# soldering_station_handle.net
KiCad netlist of a schematic drawn in Altium Designer
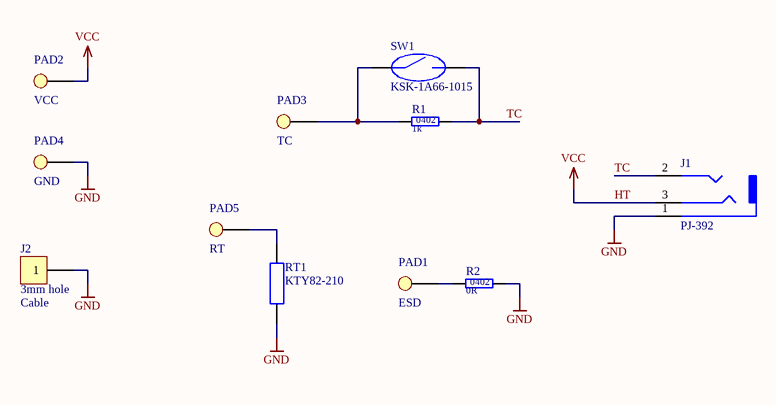
[diagram p0: soldering_station_handle.SchDoc]

(export (version "E")
  (design (tool "Eeschema 10.0.6"))
  (components
    (comp (ref "J1")
      (value "PJ-392")
      (footprint "PJ-392_Edge")
      (description "PCB Edge Mount")
      (libsource (lib "soldering_station") (part "PJ-392_Jack_Plug"))
    )
    (comp (ref "J2")
      (value "3mm hole")
      (footprint "J_HOLE3")
      (description "Single pin connector")
      (fields
        (field (name "PART NUMBER") "J_HOLE3")
        (field (name "SCH_FOOTPRINT") "Cable")
        (field (name "Comment") "Cable soldering")
      )
      (libsource (lib "Library") (part "J_PIN"))
    )
    (comp (ref "PAD1")
      (value "ESD")
      (footprint "PAD_08mm")
      (description "PCB Pad")
      (fields (field (name "PART NUMBER") "J_PAD"))
      (libsource (lib "Library") (part "PAD"))
    )
    (comp (ref "PAD2")
      (value "VCC")
      (footprint "PAD_08mm")
      (description "PCB Pad")
      (fields (field (name "PART NUMBER") "J_PAD"))
      (libsource (lib "Library") (part "PAD"))
    )
    (comp (ref "PAD3")
      (value "TC")
      (footprint "PAD_08mm")
      (description "PCB Pad")
      (fields (field (name "PART NUMBER") "J_PAD"))
      (libsource (lib "Library") (part "PAD"))
    )
    (comp (ref "PAD4")
      (value "GND")
      (footprint "PAD_08mm")
      (description "PCB Pad")
      (fields (field (name "PART NUMBER") "J_PAD"))
      (libsource (lib "Library") (part "PAD"))
    )
    (comp (ref "PAD5")
      (value "RT")
      (footprint "PAD_08mm")
      (description "PCB Pad")
      (fields (field (name "PART NUMBER") "J_PAD"))
      (libsource (lib "Library") (part "PAD"))
    )
    (comp (ref "R1")
      (value "1k")
      (footprint "R_0402_1005")
      (fields
        (field (name "SCH_FOOTPRINT") "0402")
        (field (name "PART NUMBER") "R_1k_0402_1")
        (field (name "VOLTAGE") "50V")
        (field (name "POWER") "63mW")
      )
      (libsource (lib "Library") (part "R"))
    )
    (comp (ref "R2")
      (value "0R")
      (footprint "R_0402_1005")
      (fields
        (field (name "SCH_FOOTPRINT") "0402")
        (field (name "PART NUMBER") "R_0R_0402_5")
        (field (name "VOLTAGE") "50V")
        (field (name "POWER") "100mW")
      )
      (libsource (lib "Library") (part "R"))
    )
    (comp (ref "RT1")
      (value "KTY82-210")
      (footprint "KTY82-210")
      (description "Czujnik temperatury; -55÷150°C; SOT23; SMD; 1,98kΩ")
      (libsource (lib "soldering_station") (part "KTY82-210"))
    )
    (comp (ref "SW1")
      (value "KSK-1A66-1015")
      (footprint "KSK-1A66-1015")
      (description "Kontaktron; Zakres: 10÷15AT; Pprzeł: 10W; Ø2,2x14mm; Styki: SPST-NO")
      (libsource (lib "soldering_station") (part "KSK-1A66-1015"))
    )
  )
  (nets
    (net (code "1") (name "/TC") (class "Default")
      (node (ref "J1") (pin "2") (pinfunction "RING_2") (pintype "passive"))
      (node (ref "R1") (pin "2") (pinfunction "2_2") (pintype "passive"))
      (node (ref "SW1") (pin "2") (pinfunction "2_2") (pintype "passive"))
    )
    (net (code "2") (name "GND") (class "Default")
      (node (ref "J1") (pin "1") (pinfunction "SHIELD_1") (pintype "passive"))
      (node (ref "J2") (pin "1") (pinfunction "1_1") (pintype "passive"))
      (node (ref "PAD4") (pin "1") (pintype "passive"))
      (node (ref "R2") (pin "2") (pinfunction "2_2") (pintype "passive"))
      (node (ref "RT1") (pin "2") (pinfunction "2_2") (pintype "passive"))
    )
    (net (code "3") (name "Net-(PAD1-Pad1)") (class "Default")
      (node (ref "PAD1") (pin "1") (pintype "passive"))
      (node (ref "R2") (pin "1") (pinfunction "1_1") (pintype "passive"))
    )
    (net (code "4") (name "Net-(PAD3-Pad1)") (class "Default")
      (node (ref "PAD3") (pin "1") (pintype "passive"))
      (node (ref "R1") (pin "1") (pinfunction "1_1") (pintype "passive"))
      (node (ref "SW1") (pin "1") (pinfunction "1_1") (pintype "passive"))
    )
    (net (code "5") (name "Net-(PAD5-Pad1)") (class "Default")
      (node (ref "PAD5") (pin "1") (pintype "passive"))
      (node (ref "RT1") (pin "1") (pinfunction "1_1") (pintype "passive"))
    )
    (net (code "6") (name "VCC") (class "Default")
      (node (ref "J1") (pin "3") (pinfunction "TIP_3") (pintype "passive"))
      (node (ref "PAD2") (pin "1") (pintype "passive"))
    )
  )
)
